# Ganganzeige_v2.net
KiCad netlist of a schematic drawn in EAGLE
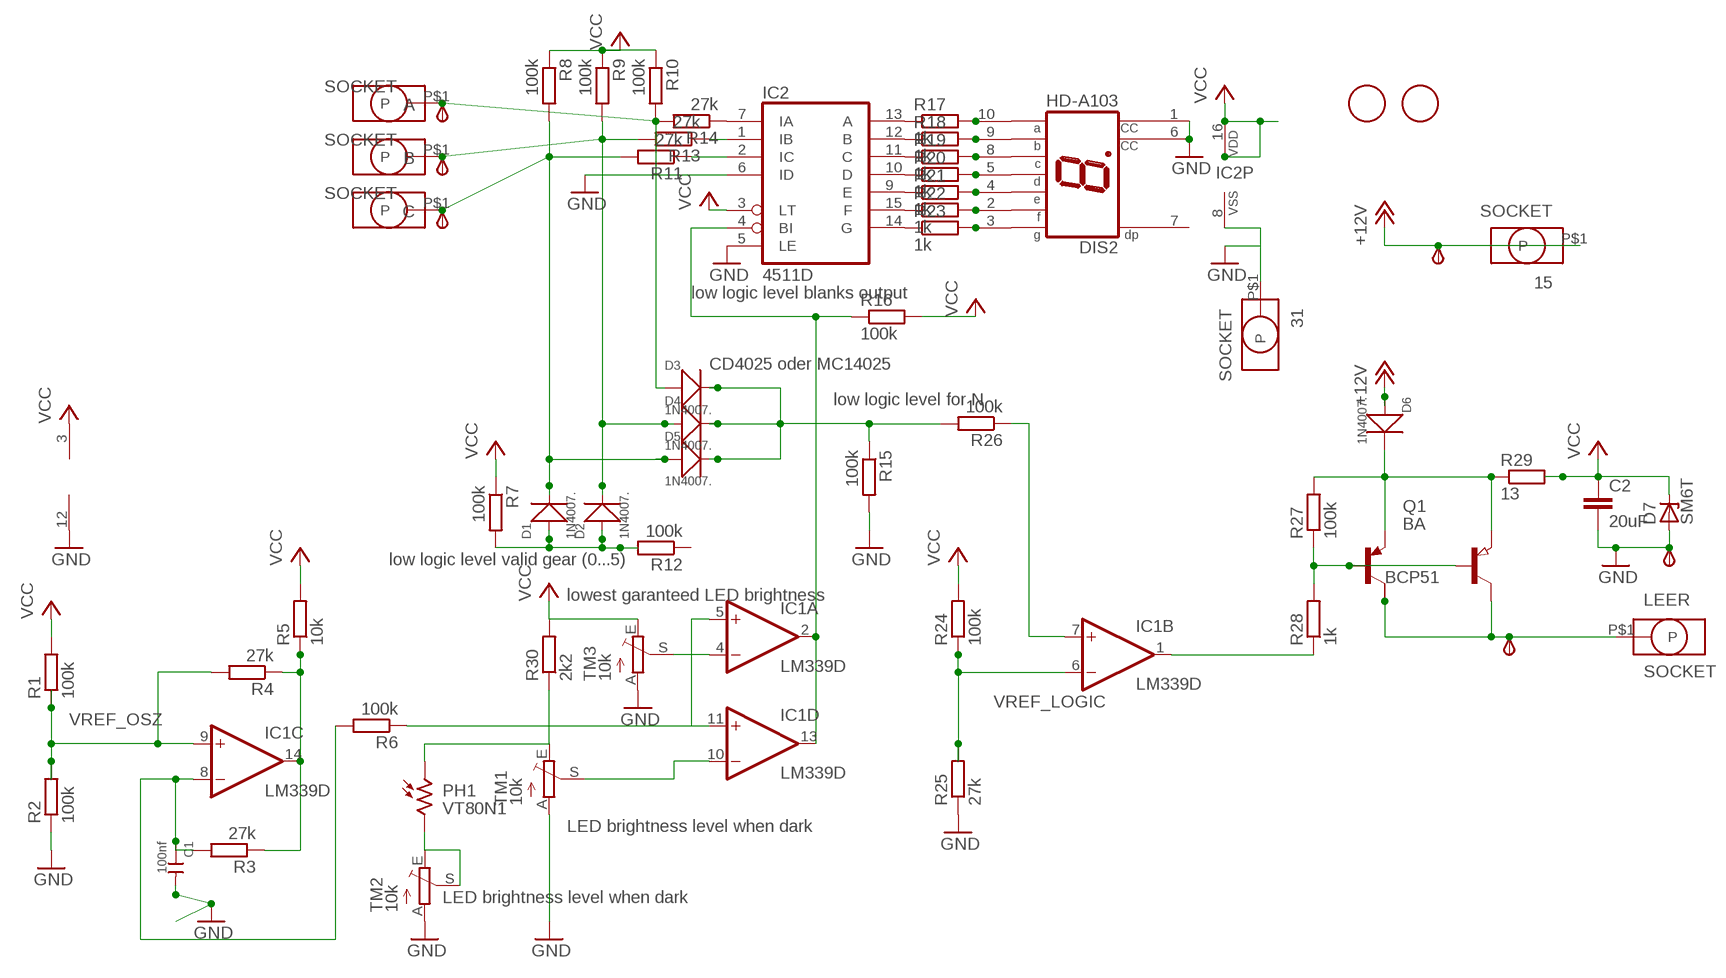
[diagram p0: schematic, sheet 1]

(export (version "E")
  (design (tool "Eeschema 10.0.6"))
  (components
    (comp (ref "15")
      (value "SOCKET")
      (footprint "eagle-import:ID2.5MM")
      (libsource (lib "eagle-import") (part "SOCKET"))
    )
    (comp (ref "15_")
      (value "TPSB2.0")
      (footprint "eagle-import:B2.0")
      (libsource (lib "eagle-import") (part "TPSB2.0"))
    )
    (comp (ref "31")
      (value "SOCKET")
      (footprint "eagle-import:ID2.5MM")
      (libsource (lib "eagle-import") (part "SOCKET"))
    )
    (comp (ref "A")
      (value "SOCKET")
      (footprint "eagle-import:ID2.5MM")
      (libsource (lib "eagle-import") (part "SOCKET"))
    )
    (comp (ref "A_")
      (value "TPSB2.0")
      (footprint "eagle-import:B2.0")
      (libsource (lib "eagle-import") (part "TPSB2.0"))
    )
    (comp (ref "B")
      (value "SOCKET")
      (footprint "eagle-import:ID2.5MM")
      (libsource (lib "eagle-import") (part "SOCKET"))
    )
    (comp (ref "B_")
      (value "TPSB2.0")
      (footprint "eagle-import:B2.0")
      (libsource (lib "eagle-import") (part "TPSB2.0"))
    )
    (comp (ref "C")
      (value "SOCKET")
      (footprint "eagle-import:ID2.5MM")
      (libsource (lib "eagle-import") (part "SOCKET"))
    )
    (comp (ref "C1")
      (value "100nf")
      (footprint "eagle-import:C0805")
      (fields (field (name "MPN") "CC0805KRX7R9BB104"))
      (libsource (lib "eagle-import") (part "CERAMIC-100NF-50V-10%-X7R(0805)"))
    )
    (comp (ref "C2")
      (value "20uF")
      (footprint "eagle-import:C1206K")
      (libsource (lib "eagle-import") (part "C-EUC1206K"))
    )
    (comp (ref "C_")
      (value "TPSB2.0")
      (footprint "eagle-import:B2.0")
      (libsource (lib "eagle-import") (part "TPSB2.0"))
    )
    (comp (ref "D1")
      (value "1N4007.")
      (footprint "eagle-import:DO-214AC")
      (fields (field (name "MPN") "1N4007"))
      (libsource (lib "eagle-import") (part "DIODE-GEN-PURPOSE-1KV-1A(DO-214AC)"))
    )
    (comp (ref "D2")
      (value "1N4007.")
      (footprint "eagle-import:DO-214AC")
      (fields (field (name "MPN") "1N4007"))
      (libsource (lib "eagle-import") (part "DIODE-GEN-PURPOSE-1KV-1A(DO-214AC)"))
    )
    (comp (ref "D3")
      (value "1N4007.")
      (footprint "eagle-import:DO-214AC")
      (fields (field (name "MPN") "1N4007"))
      (libsource (lib "eagle-import") (part "DIODE-GEN-PURPOSE-1KV-1A(DO-214AC)"))
    )
    (comp (ref "D4")
      (value "1N4007.")
      (footprint "eagle-import:DO-214AC")
      (fields (field (name "MPN") "1N4007"))
      (libsource (lib "eagle-import") (part "DIODE-GEN-PURPOSE-1KV-1A(DO-214AC)"))
    )
    (comp (ref "D5")
      (value "1N4007.")
      (footprint "eagle-import:DO-214AC")
      (fields (field (name "MPN") "1N4007"))
      (libsource (lib "eagle-import") (part "DIODE-GEN-PURPOSE-1KV-1A(DO-214AC)"))
    )
    (comp (ref "D6")
      (value "1N4007.")
      (footprint "eagle-import:DO-214AC")
      (fields (field (name "MPN") "1N4007"))
      (libsource (lib "eagle-import") (part "DIODE-GEN-PURPOSE-1KV-1A(DO-214AC)"))
    )
    (comp (ref "D7")
      (value "SM6T")
      (footprint "eagle-import:DO214AA")
      (libsource (lib "eagle-import") (part "SM6T"))
    )
    (comp (ref "DIS2")
      (value "HD-A103")
      (footprint "eagle-import:HDSP-A")
      (libsource (lib "eagle-import") (part "HD-A103"))
    )
    (comp (ref "FID1")
      (value "FIDUCIAL")
      (footprint "eagle-import:FIDUCIAL_1MM")
      (libsource (lib "eagle-import") (part "FIDUCIAL"))
    )
    (comp (ref "FID2")
      (value "FIDUCIAL")
      (footprint "eagle-import:FIDUCIAL_1MM")
      (libsource (lib "eagle-import") (part "FIDUCIAL"))
    )
    (comp (ref "GND_")
      (value "TPSB2.0")
      (footprint "eagle-import:B2.0")
      (libsource (lib "eagle-import") (part "TPSB2.0"))
    )
    (comp (ref "IC1")
      (value "LM339D")
      (footprint "eagle-import:SO14")
      (libsource (lib "eagle-import") (part "LM339D"))
    )
    (comp (ref "IC2")
      (value "4511D")
      (footprint "eagle-import:SO16")
      (libsource (lib "eagle-import") (part "4511D"))
    )
    (comp (ref "LEER")
      (value "SOCKET")
      (footprint "eagle-import:ID2.5MM")
      (libsource (lib "eagle-import") (part "SOCKET"))
    )
    (comp (ref "LEER_")
      (value "TPSB2.0")
      (footprint "eagle-import:B2.0")
      (libsource (lib "eagle-import") (part "TPSB2.0"))
    )
    (comp (ref "PH1")
      (value "VT80N1")
      (footprint "eagle-import:VT800")
      (libsource (lib "eagle-import") (part "VT80N1"))
    )
    (comp (ref "Q1")
      (value "BA")
      (footprint "eagle-import:SOT89")
      (libsource (lib "eagle-import") (part "PNP-TRANSISTOR_SOT89"))
    )
    (comp (ref "R1")
      (value "100k")
      (footprint "eagle-import:R0805")
      (libsource (lib "eagle-import") (part "R-EU_R0805"))
    )
    (comp (ref "R2")
      (value "100k")
      (footprint "eagle-import:R0805")
      (libsource (lib "eagle-import") (part "R-EU_R0805"))
    )
    (comp (ref "R3")
      (value "27k")
      (footprint "eagle-import:R0805")
      (libsource (lib "eagle-import") (part "R-EU_R0805"))
    )
    (comp (ref "R4")
      (value "27k")
      (footprint "eagle-import:R0805")
      (libsource (lib "eagle-import") (part "R-EU_R0805"))
    )
    (comp (ref "R5")
      (value "10k")
      (footprint "eagle-import:R0805")
      (libsource (lib "eagle-import") (part "R-EU_R0805"))
    )
    (comp (ref "R6")
      (value "100k")
      (footprint "eagle-import:R0805")
      (libsource (lib "eagle-import") (part "R-EU_R0805"))
    )
    (comp (ref "R7")
      (value "100k")
      (footprint "eagle-import:R0805")
      (libsource (lib "eagle-import") (part "R-EU_R0805"))
    )
    (comp (ref "R8")
      (value "100k")
      (footprint "eagle-import:R0805")
      (libsource (lib "eagle-import") (part "R-EU_R0805"))
    )
    (comp (ref "R9")
      (value "100k")
      (footprint "eagle-import:R0805")
      (libsource (lib "eagle-import") (part "R-EU_R0805"))
    )
    (comp (ref "R10")
      (value "100k")
      (footprint "eagle-import:R0805")
      (libsource (lib "eagle-import") (part "R-EU_R0805"))
    )
    (comp (ref "R11")
      (value "27k")
      (footprint "eagle-import:R0805")
      (libsource (lib "eagle-import") (part "R-EU_R0805"))
    )
    (comp (ref "R12")
      (value "100k")
      (footprint "eagle-import:R0805")
      (libsource (lib "eagle-import") (part "R-EU_R0805"))
    )
    (comp (ref "R13")
      (value "27k")
      (footprint "eagle-import:R0805")
      (libsource (lib "eagle-import") (part "R-EU_R0805"))
    )
    (comp (ref "R14")
      (value "27k")
      (footprint "eagle-import:R0805")
      (libsource (lib "eagle-import") (part "R-EU_R0805"))
    )
    (comp (ref "R15")
      (value "100k")
      (footprint "eagle-import:R0805")
      (libsource (lib "eagle-import") (part "R-EU_R0805"))
    )
    (comp (ref "R16")
      (value "100k")
      (footprint "eagle-import:R0805")
      (libsource (lib "eagle-import") (part "R-EU_R0805"))
    )
    (comp (ref "R17")
      (value "1k")
      (footprint "eagle-import:R0805")
      (libsource (lib "eagle-import") (part "R-EU_R0805"))
    )
    (comp (ref "R18")
      (value "1k")
      (footprint "eagle-import:R0805")
      (libsource (lib "eagle-import") (part "R-EU_R0805"))
    )
    (comp (ref "R19")
      (value "1k")
      (footprint "eagle-import:R0805")
      (libsource (lib "eagle-import") (part "R-EU_R0805"))
    )
    (comp (ref "R20")
      (value "1k")
      (footprint "eagle-import:R0805")
      (libsource (lib "eagle-import") (part "R-EU_R0805"))
    )
    (comp (ref "R21")
      (value "1k")
      (footprint "eagle-import:R0805")
      (libsource (lib "eagle-import") (part "R-EU_R0805"))
    )
    (comp (ref "R22")
      (value "1k")
      (footprint "eagle-import:R0805")
      (libsource (lib "eagle-import") (part "R-EU_R0805"))
    )
    (comp (ref "R23")
      (value "1k")
      (footprint "eagle-import:R0805")
      (libsource (lib "eagle-import") (part "R-EU_R0805"))
    )
    (comp (ref "R24")
      (value "100k")
      (footprint "eagle-import:R0805")
      (libsource (lib "eagle-import") (part "R-EU_R0805"))
    )
    (comp (ref "R25")
      (value "27k")
      (footprint "eagle-import:R0805")
      (libsource (lib "eagle-import") (part "R-EU_R0805"))
    )
    (comp (ref "R26")
      (value "100k")
      (footprint "eagle-import:R0805")
      (libsource (lib "eagle-import") (part "R-EU_R0805"))
    )
    (comp (ref "R27")
      (value "100k")
      (footprint "eagle-import:R0805")
      (libsource (lib "eagle-import") (part "R-EU_R0805"))
    )
    (comp (ref "R28")
      (value "1k")
      (footprint "eagle-import:R0805")
      (libsource (lib "eagle-import") (part "R-EU_R0805"))
    )
    (comp (ref "R29")
      (value "13")
      (footprint "eagle-import:R1206")
      (libsource (lib "eagle-import") (part "R-EU_R1206"))
    )
    (comp (ref "R30")
      (value "2k2")
      (footprint "eagle-import:R0805")
      (libsource (lib "eagle-import") (part "R-EU_R0805"))
    )
    (comp (ref "T")
      (value "BCP53T1")
      (footprint "eagle-import:SOT223")
      (fields (field (name "T") "BCP51"))
      (libsource (lib "eagle-import") (part "BCP53T1"))
    )
    (comp (ref "TM1")
      (value "10k")
      (footprint "eagle-import:S63X")
      (libsource (lib "eagle-import") (part "TRIM_EU-S63X"))
    )
    (comp (ref "TM2")
      (value "10k")
      (footprint "eagle-import:S63X")
      (libsource (lib "eagle-import") (part "TRIM_EU-S63X"))
    )
    (comp (ref "TM3")
      (value "10k")
      (footprint "eagle-import:S63X")
      (libsource (lib "eagle-import") (part "TRIM_EU-S63X"))
    )
  )
  (nets
    (net (code "1") (name "+12V") (class "Default")
      (node (ref "15") (pin "P$1") (pinfunction "P_P$1") (pintype "bidirectional"))
      (node (ref "15_") (pin "TP") (pinfunction "PP_TP") (pintype "input"))
      (node (ref "D6") (pin "1") (pinfunction "+_1") (pintype "passive"))
    )
    (net (code "2") (name "/VREF_LOGIC") (class "Default")
      (node (ref "IC1") (pin "6") (pinfunction "-IN_6") (pintype "input"))
      (node (ref "R24") (pin "1") (pinfunction "1_1") (pintype "passive"))
      (node (ref "R25") (pin "2") (pinfunction "2_2") (pintype "passive"))
    )
    (net (code "3") (name "/VREF_OSZ") (class "Default")
      (node (ref "IC1") (pin "9") (pinfunction "+IN_9") (pintype "input"))
      (node (ref "R1") (pin "1") (pinfunction "1_1") (pintype "passive"))
      (node (ref "R2") (pin "2") (pinfunction "2_2") (pintype "passive"))
      (node (ref "R4") (pin "2") (pinfunction "2_2") (pintype "passive"))
    )
    (net (code "4") (name "GND") (class "Default")
      (node (ref "31") (pin "P$1") (pinfunction "P_P$1") (pintype "bidirectional"))
      (node (ref "C1") (pin "2") (pinfunction "2_2") (pintype "passive"))
      (node (ref "C2") (pin "2") (pinfunction "2_2") (pintype "passive"))
      (node (ref "D7") (pin "A") (pinfunction "A_A") (pintype "passive"))
      (node (ref "DIS2") (pin "1") (pinfunction "CC_1") (pintype "passive"))
      (node (ref "DIS2") (pin "6") (pinfunction "CC_6") (pintype "passive"))
      (node (ref "GND_") (pin "TP") (pinfunction "PP_TP") (pintype "input"))
      (node (ref "IC1") (pin "12") (pinfunction "GND_12") (pintype "power_in"))
      (node (ref "IC2") (pin "5") (pinfunction "LE_5") (pintype "input"))
      (node (ref "IC2") (pin "6") (pinfunction "ID_6") (pintype "input"))
      (node (ref "IC2") (pin "8") (pinfunction "VSS_8") (pintype "power_in"))
      (node (ref "R15") (pin "2") (pinfunction "2_2") (pintype "passive"))
      (node (ref "R2") (pin "1") (pinfunction "1_1") (pintype "passive"))
      (node (ref "R25") (pin "1") (pinfunction "1_1") (pintype "passive"))
      (node (ref "TM1") (pin "A") (pinfunction "A_A") (pintype "passive"))
      (node (ref "TM2") (pin "A") (pinfunction "A_A") (pintype "passive"))
      (node (ref "TM3") (pin "A") (pinfunction "A_A") (pintype "passive"))
    )
    (net (code "5") (name "Net-(A-P)") (class "Default")
      (node (ref "A") (pin "P$1") (pinfunction "P_P$1") (pintype "bidirectional"))
      (node (ref "A_") (pin "TP") (pinfunction "PP_TP") (pintype "input"))
      (node (ref "D3") (pin "1") (pinfunction "+_1") (pintype "passive"))
      (node (ref "R10") (pin "2") (pinfunction "2_2") (pintype "passive"))
      (node (ref "R14") (pin "2") (pinfunction "2_2") (pintype "passive"))
    )
    (net (code "6") (name "Net-(B-P)") (class "Default")
      (node (ref "B") (pin "P$1") (pinfunction "P_P$1") (pintype "bidirectional"))
      (node (ref "B_") (pin "TP") (pinfunction "PP_TP") (pintype "input"))
      (node (ref "D2") (pin "2") (pinfunction "-_2") (pintype "passive"))
      (node (ref "D4") (pin "1") (pinfunction "+_1") (pintype "passive"))
      (node (ref "R13") (pin "2") (pinfunction "2_2") (pintype "passive"))
      (node (ref "R9") (pin "2") (pinfunction "2_2") (pintype "passive"))
    )
    (net (code "7") (name "Net-(C-P)") (class "Default")
      (node (ref "C") (pin "P$1") (pinfunction "P_P$1") (pintype "bidirectional"))
      (node (ref "C_") (pin "TP") (pinfunction "PP_TP") (pintype "input"))
      (node (ref "D1") (pin "2") (pinfunction "-_2") (pintype "passive"))
      (node (ref "D5") (pin "1") (pinfunction "+_1") (pintype "passive"))
      (node (ref "R11") (pin "2") (pinfunction "2_2") (pintype "passive"))
      (node (ref "R8") (pin "2") (pinfunction "2_2") (pintype "passive"))
    )
    (net (code "8") (name "Net-(D1-+)") (class "Default")
      (node (ref "D1") (pin "1") (pinfunction "+_1") (pintype "passive"))
      (node (ref "D2") (pin "1") (pinfunction "+_1") (pintype "passive"))
      (node (ref "R12") (pin "2") (pinfunction "2_2") (pintype "passive"))
      (node (ref "R7") (pin "2") (pinfunction "2_2") (pintype "passive"))
    )
    (net (code "9") (name "Net-(D3--)") (class "Default")
      (node (ref "D3") (pin "2") (pinfunction "-_2") (pintype "passive"))
      (node (ref "D4") (pin "2") (pinfunction "-_2") (pintype "passive"))
      (node (ref "D5") (pin "2") (pinfunction "-_2") (pintype "passive"))
      (node (ref "R15") (pin "1") (pinfunction "1_1") (pintype "passive"))
      (node (ref "R26") (pin "2") (pinfunction "2_2") (pintype "passive"))
    )
    (net (code "10") (name "Net-(D6--)") (class "Default")
      (node (ref "D6") (pin "2") (pinfunction "-_2") (pintype "passive"))
      (node (ref "Q1") (pin "3") (pinfunction "E_3") (pintype "passive"))
      (node (ref "R27") (pin "2") (pinfunction "2_2") (pintype "passive"))
      (node (ref "R29") (pin "1") (pinfunction "1_1") (pintype "passive"))
      (node (ref "T") (pin "3") (pinfunction "E_3") (pintype "passive"))
    )
    (net (code "11") (name "Net-(DIS2-A)") (class "Default")
      (node (ref "DIS2") (pin "10") (pinfunction "A_10") (pintype "passive"))
      (node (ref "R17") (pin "2") (pinfunction "2_2") (pintype "passive"))
    )
    (net (code "12") (name "Net-(DIS2-B)") (class "Default")
      (node (ref "DIS2") (pin "9") (pinfunction "B_9") (pintype "passive"))
      (node (ref "R18") (pin "2") (pinfunction "2_2") (pintype "passive"))
    )
    (net (code "13") (name "Net-(DIS2-C)") (class "Default")
      (node (ref "DIS2") (pin "8") (pinfunction "C_8") (pintype "passive"))
      (node (ref "R19") (pin "2") (pinfunction "2_2") (pintype "passive"))
    )
    (net (code "14") (name "Net-(DIS2-D)") (class "Default")
      (node (ref "DIS2") (pin "5") (pinfunction "D_5") (pintype "passive"))
      (node (ref "R20") (pin "2") (pinfunction "2_2") (pintype "passive"))
    )
    (net (code "15") (name "Net-(DIS2-E)") (class "Default")
      (node (ref "DIS2") (pin "4") (pinfunction "E_4") (pintype "passive"))
      (node (ref "R21") (pin "2") (pinfunction "2_2") (pintype "passive"))
    )
    (net (code "16") (name "Net-(DIS2-F)") (class "Default")
      (node (ref "DIS2") (pin "2") (pinfunction "F_2") (pintype "passive"))
      (node (ref "R22") (pin "2") (pinfunction "2_2") (pintype "passive"))
    )
    (net (code "17") (name "Net-(DIS2-G)") (class "Default")
      (node (ref "DIS2") (pin "3") (pinfunction "G_3") (pintype "passive"))
      (node (ref "R23") (pin "2") (pinfunction "2_2") (pintype "passive"))
    )
    (net (code "18") (name "Net-(IC1A-+IN)") (class "Default")
      (node (ref "IC1") (pin "11") (pinfunction "+IN_11") (pintype "input"))
      (node (ref "IC1") (pin "5") (pinfunction "+IN_5") (pintype "input"))
      (node (ref "R6") (pin "1") (pinfunction "1_1") (pintype "passive"))
    )
    (net (code "19") (name "Net-(IC1A--IN)") (class "Default")
      (node (ref "IC1") (pin "4") (pinfunction "-IN_4") (pintype "input"))
      (node (ref "TM3") (pin "S") (pinfunction "S_S") (pintype "passive"))
    )
    (net (code "20") (name "Net-(IC1A-OUT)") (class "Default")
      (node (ref "IC1") (pin "13") (pinfunction "OUT_13") (pintype "open_collector"))
      (node (ref "IC1") (pin "2") (pinfunction "OUT_2") (pintype "open_collector"))
      (node (ref "IC2") (pin "4") (pinfunction "BI_4") (pintype "input"))
      (node (ref "R16") (pin "1") (pinfunction "1_1") (pintype "passive"))
    )
    (net (code "21") (name "Net-(IC1B-+IN)") (class "Default")
      (node (ref "IC1") (pin "7") (pinfunction "+IN_7") (pintype "input"))
      (node (ref "R26") (pin "1") (pinfunction "1_1") (pintype "passive"))
    )
    (net (code "22") (name "Net-(IC1B-OUT)") (class "Default")
      (node (ref "IC1") (pin "1") (pinfunction "OUT_1") (pintype "open_collector"))
      (node (ref "R28") (pin "1") (pinfunction "1_1") (pintype "passive"))
    )
    (net (code "23") (name "Net-(IC1C--IN)") (class "Default")
      (node (ref "C1") (pin "1") (pinfunction "1_1") (pintype "passive"))
      (node (ref "IC1") (pin "8") (pinfunction "-IN_8") (pintype "input"))
      (node (ref "R3") (pin "2") (pinfunction "2_2") (pintype "passive"))
      (node (ref "R6") (pin "2") (pinfunction "2_2") (pintype "passive"))
    )
    (net (code "24") (name "Net-(IC1C-OUT)") (class "Default")
      (node (ref "IC1") (pin "14") (pinfunction "OUT_14") (pintype "open_collector"))
      (node (ref "R3") (pin "1") (pinfunction "1_1") (pintype "passive"))
      (node (ref "R4") (pin "1") (pinfunction "1_1") (pintype "passive"))
      (node (ref "R5") (pin "1") (pinfunction "1_1") (pintype "passive"))
    )
    (net (code "25") (name "Net-(IC1D--IN)") (class "Default")
      (node (ref "IC1") (pin "10") (pinfunction "-IN_10") (pintype "input"))
      (node (ref "TM1") (pin "S") (pinfunction "S_S") (pintype "passive"))
    )
    (net (code "26") (name "Net-(IC2A-A)") (class "Default")
      (node (ref "IC2") (pin "13") (pinfunction "A_13") (pintype "output"))
      (node (ref "R17") (pin "1") (pinfunction "1_1") (pintype "passive"))
    )
    (net (code "27") (name "Net-(IC2A-B)") (class "Default")
      (node (ref "IC2") (pin "12") (pinfunction "B_12") (pintype "output"))
      (node (ref "R18") (pin "1") (pinfunction "1_1") (pintype "passive"))
    )
    (net (code "28") (name "Net-(IC2A-C)") (class "Default")
      (node (ref "IC2") (pin "11") (pinfunction "C_11") (pintype "output"))
      (node (ref "R19") (pin "1") (pinfunction "1_1") (pintype "passive"))
    )
    (net (code "29") (name "Net-(IC2A-D)") (class "Default")
      (node (ref "IC2") (pin "10") (pinfunction "D_10") (pintype "output"))
      (node (ref "R20") (pin "1") (pinfunction "1_1") (pintype "passive"))
    )
    (net (code "30") (name "Net-(IC2A-E)") (class "Default")
      (node (ref "IC2") (pin "9") (pinfunction "E_9") (pintype "output"))
      (node (ref "R21") (pin "1") (pinfunction "1_1") (pintype "passive"))
    )
    (net (code "31") (name "Net-(IC2A-F)") (class "Default")
      (node (ref "IC2") (pin "15") (pinfunction "F_15") (pintype "output"))
      (node (ref "R22") (pin "1") (pinfunction "1_1") (pintype "passive"))
    )
    (net (code "32") (name "Net-(IC2A-G)") (class "Default")
      (node (ref "IC2") (pin "14") (pinfunction "G_14") (pintype "output"))
      (node (ref "R23") (pin "1") (pinfunction "1_1") (pintype "passive"))
    )
    (net (code "33") (name "Net-(IC2A-IA)") (class "Default")
      (node (ref "IC2") (pin "7") (pinfunction "IA_7") (pintype "input"))
      (node (ref "R14") (pin "1") (pinfunction "1_1") (pintype "passive"))
    )
    (net (code "34") (name "Net-(IC2A-IB)") (class "Default")
      (node (ref "IC2") (pin "1") (pinfunction "IB_1") (pintype "input"))
      (node (ref "R13") (pin "1") (pinfunction "1_1") (pintype "passive"))
    )
    (net (code "35") (name "Net-(IC2A-IC)") (class "Default")
      (node (ref "IC2") (pin "2") (pinfunction "IC_2") (pintype "input"))
      (node (ref "R11") (pin "1") (pinfunction "1_1") (pintype "passive"))
    )
    (net (code "36") (name "Net-(LEER-P)") (class "Default")
      (node (ref "LEER") (pin "P$1") (pinfunction "P_P$1") (pintype "bidirectional"))
      (node (ref "LEER_") (pin "TP") (pinfunction "PP_TP") (pintype "input"))
      (node (ref "Q1") (pin "2") (pinfunction "C_2") (pintype "passive"))
      (node (ref "T") (pin "2") (pinfunction "C_2") (pintype "passive"))
    )
    (net (code "37") (name "Net-(PH1-Pad1)") (class "Default")
      (node (ref "PH1") (pin "1") (pinfunction "1_1") (pintype "passive"))
      (node (ref "R30") (pin "1") (pinfunction "1_1") (pintype "passive"))
      (node (ref "TM1") (pin "E") (pinfunction "E_E") (pintype "passive"))
    )
    (net (code "38") (name "Net-(PH1-Pad2)") (class "Default")
      (node (ref "PH1") (pin "2") (pinfunction "2_2") (pintype "passive"))
      (node (ref "TM2") (pin "E") (pinfunction "E_E") (pintype "passive"))
      (node (ref "TM2") (pin "S") (pinfunction "S_S") (pintype "passive"))
    )
    (net (code "39") (name "Net-(Q1-B)") (class "Default")
      (node (ref "Q1") (pin "1") (pinfunction "B_1") (pintype "passive"))
      (node (ref "R27") (pin "1") (pinfunction "1_1") (pintype "passive"))
      (node (ref "R28") (pin "2") (pinfunction "2_2") (pintype "passive"))
      (node (ref "T") (pin "1") (pinfunction "B_1") (pintype "passive"))
    )
    (net (code "40") (name "VCC") (class "Default")
      (node (ref "C2") (pin "1") (pinfunction "1_1") (pintype "passive"))
      (node (ref "D7") (pin "C") (pinfunction "C_C") (pintype "passive"))
      (node (ref "IC1") (pin "3") (pinfunction "V+_3") (pintype "power_in"))
      (node (ref "IC2") (pin "16") (pinfunction "VDD_16") (pintype "power_in"))
      (node (ref "IC2") (pin "3") (pinfunction "LT_3") (pintype "input"))
      (node (ref "R1") (pin "2") (pinfunction "2_2") (pintype "passive"))
      (node (ref "R10") (pin "1") (pinfunction "1_1") (pintype "passive"))
      (node (ref "R16") (pin "2") (pinfunction "2_2") (pintype "passive"))
      (node (ref "R24") (pin "2") (pinfunction "2_2") (pintype "passive"))
      (node (ref "R29") (pin "2") (pinfunction "2_2") (pintype "passive"))
      (node (ref "R30") (pin "2") (pinfunction "2_2") (pintype "passive"))
      (node (ref "R5") (pin "2") (pinfunction "2_2") (pintype "passive"))
      (node (ref "R7") (pin "1") (pinfunction "1_1") (pintype "passive"))
      (node (ref "R8") (pin "1") (pinfunction "1_1") (pintype "passive"))
      (node (ref "R9") (pin "1") (pinfunction "1_1") (pintype "passive"))
      (node (ref "TM3") (pin "E") (pinfunction "E_E") (pintype "passive"))
    )
    (net (code "41") (name "unconnected-(DIS2-DP-Pad7)") (class "Default")
      (node (ref "DIS2") (pin "7") (pinfunction "DP_7") (pintype "passive"))
    )
    (net (code "42") (name "unconnected-(R12-Pad1)") (class "Default")
      (node (ref "R12") (pin "1") (pinfunction "1_1") (pintype "passive"))
    )
    (net (code "43") (name "unconnected-(T-C{slash}-Pad4)") (class "Default")
      (node (ref "T") (pin "4") (pinfunction "C/_4") (pintype "passive"))
    )
  )
)
